# BV100011_Ethernet.net
KiCad netlist of a schematic drawn in Altium Designer
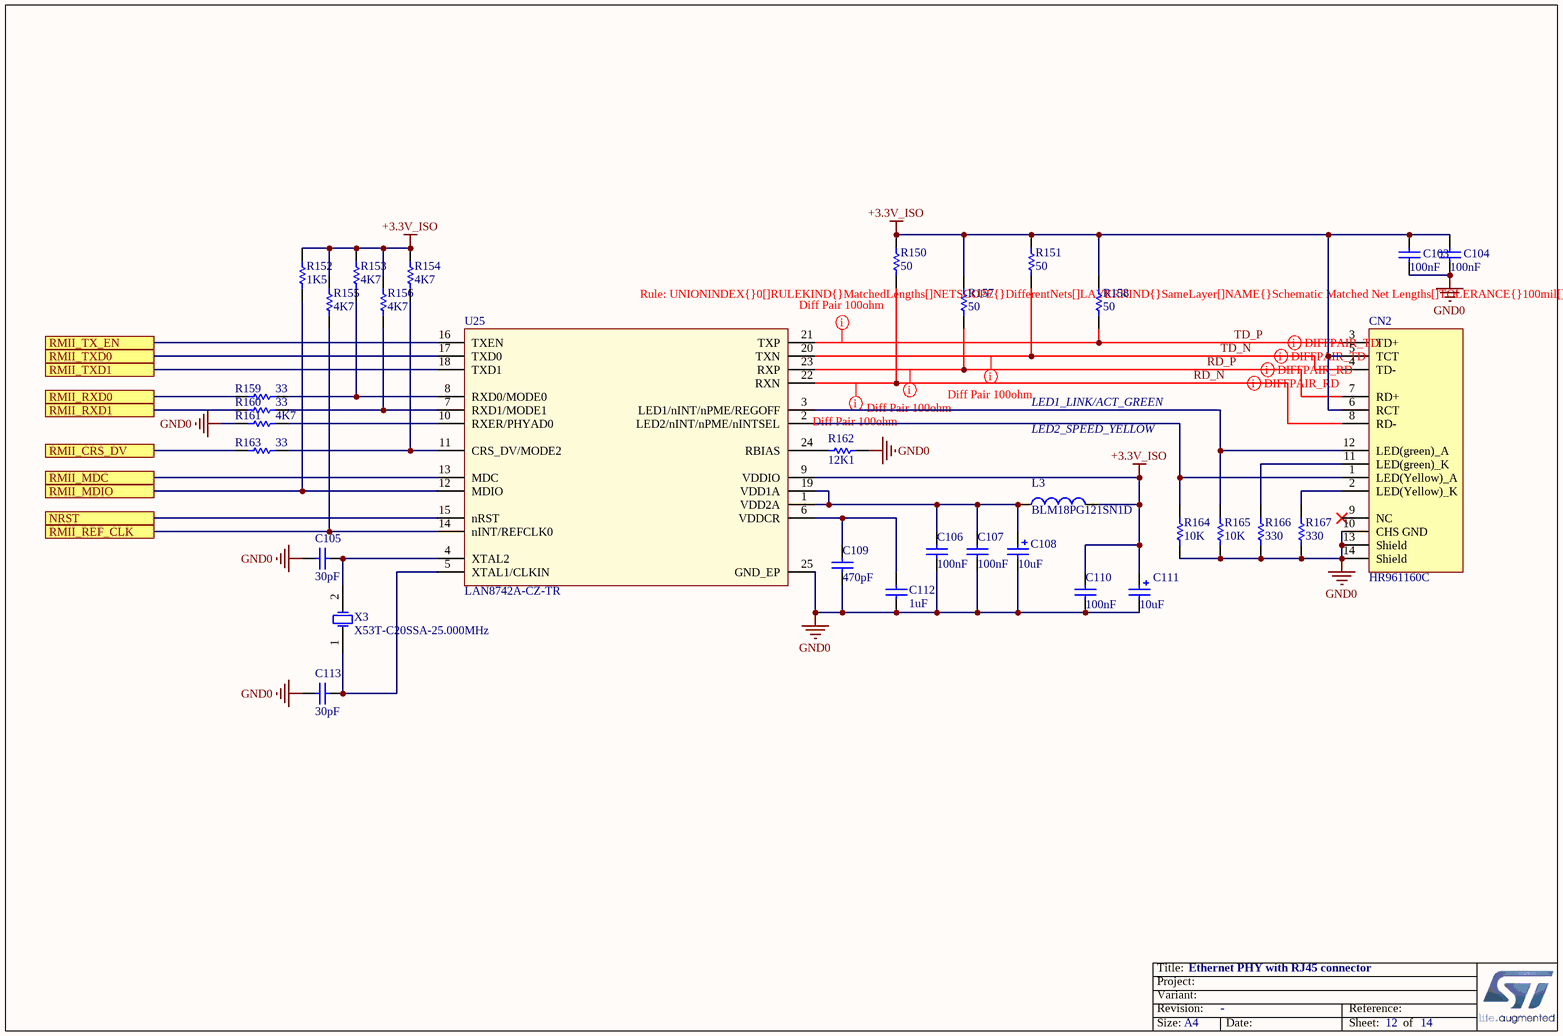
[diagram p0: BV100011_Ethernet.SchDoc]

(export (version "E")
  (design (tool "Eeschema 10.0.6"))
  (components
    (comp (ref "C103")
      (value "100nF")
      (footprint "0402C")
      (description "Capacitor,100nF,16V,X7R,10%,0402,YAGEO")
      (libsource (lib "MCD_TOOLS") (part "Cap_100nF_X7R_10%_0402"))
    )
    (comp (ref "C104")
      (value "100nF")
      (footprint "0402C")
      (description "Capacitor,100nF,16V,X7R,10%,0402,YAGEO")
      (libsource (lib "MCD_TOOLS") (part "Cap_100nF_X7R_10%_0402"))
    )
    (comp (ref "C105")
      (value "30pF")
      (footprint "0603C")
      (description "Capacitor 0402 / 0603 / 0805")
      (libsource (lib "MCD_TOOLS") (part "Capacitor_ST"))
    )
    (comp (ref "C106")
      (value "100nF")
      (footprint "0402C")
      (description "Capacitor,100nF,16V,X7R,10%,0402,YAGEO")
      (libsource (lib "MCD_TOOLS") (part "Cap_100nF_X7R_10%_0402"))
    )
    (comp (ref "C107")
      (value "100nF")
      (footprint "0402C")
      (description "Capacitor,100nF,16V,X7R,10%,0402,YAGEO")
      (libsource (lib "MCD_TOOLS") (part "Cap_100nF_X7R_10%_0402"))
    )
    (comp (ref "C108")
      (value "10uF")
      (footprint "TAN-A")
      (description "Polarized Capacitor,10uF,10V,10%,typeA,VISHAY")
      (libsource (lib "MCD_TOOLS") (part "Cap_10uF_POL_10%_TANA"))
    )
    (comp (ref "C109")
      (value "470pF")
      (footprint "0402C")
      (description "Capacitor,470pF,16V,X7R,10%,0402,YAGEO")
      (libsource (lib "MCD_TOOLS") (part "Cap_470pF_X7R_10%_0402"))
    )
    (comp (ref "C110")
      (value "100nF")
      (footprint "0402C")
      (description "Capacitor,100nF,16V,X7R,10%,0402,YAGEO")
      (libsource (lib "MCD_TOOLS") (part "Cap_100nF_X7R_10%_0402"))
    )
    (comp (ref "C111")
      (value "10uF")
      (footprint "TAN-A")
      (description "Polarized Capacitor,10uF,10V,10%,typeA,VISHAY")
      (libsource (lib "MCD_TOOLS") (part "Cap_10uF_POL_10%_TANA"))
    )
    (comp (ref "C112")
      (value "1uF")
      (footprint "0603C")
      (description "Capacitor,1uF,16V,X5R,10%,0603,YAGEO")
      (libsource (lib "MCD_TOOLS") (part "Cap_1uF_X5R_10%_0603"))
    )
    (comp (ref "C113")
      (value "30pF")
      (footprint "0603C")
      (description "Capacitor 0402 / 0603 / 0805")
      (libsource (lib "MCD_TOOLS") (part "Capacitor_ST"))
    )
    (comp (ref "CN2")
      (value "HR961160C")
      (footprint "RJ45_HR961160C")
      (description "100 Base-TX (Fast Ethernet) SMD RJ45 single port (1x1) with LEDS Integrated Magnetics Connector")
      (libsource (lib "MCD_TOOLS") (part "HR961160C"))
    )
    (comp (ref "L3")
      (value "BLM18PG121SN1D")
      (footprint "0603L")
      (description "Bead,120R,2A,0603,BLM18PG121SN1D,MURATA")
      (libsource (lib "MCD_TOOLS") (part "BEAD_120R_2A_0603"))
    )
    (comp (ref "R150")
      (value "50")
      (footprint "0402R")
      (description "Resistor,50,0402,1%,YAGEO")
      (libsource (lib "MCD_TOOLS") (part "Res_50_1%_0402"))
    )
    (comp (ref "R151")
      (value "50")
      (footprint "0402R")
      (description "Resistor,50,0402,1%,YAGEO")
      (libsource (lib "MCD_TOOLS") (part "Res_50_1%_0402"))
    )
    (comp (ref "R152")
      (value "1K5")
      (footprint "0402R")
      (description "Resistor,1K5,0402,1%,YAGEO")
      (libsource (lib "MCD_TOOLS") (part "Res_1K5_1%_0402"))
    )
    (comp (ref "R153")
      (value "4K7")
      (footprint "0402R")
      (description "Resistor,4K7,0402,1%,YAGEO")
      (libsource (lib "MCD_TOOLS") (part "Res_4K7_1%_0402"))
    )
    (comp (ref "R154")
      (value "4K7")
      (footprint "0402R")
      (description "Resistor,4K7,0402,1%,YAGEO")
      (libsource (lib "MCD_TOOLS") (part "Res_4K7_1%_0402"))
    )
    (comp (ref "R155")
      (value "4K7")
      (footprint "0402R")
      (description "Resistor,4K7,0402,1%,YAGEO")
      (libsource (lib "MCD_TOOLS") (part "Res_4K7_1%_0402"))
    )
    (comp (ref "R156")
      (value "4K7")
      (footprint "0402R")
      (description "Resistor,4K7,0402,1%,YAGEO")
      (libsource (lib "MCD_TOOLS") (part "Res_4K7_1%_0402"))
    )
    (comp (ref "R157")
      (value "50")
      (footprint "0402R")
      (description "Resistor,50,0402,1%,YAGEO")
      (libsource (lib "MCD_TOOLS") (part "Res_50_1%_0402"))
    )
    (comp (ref "R158")
      (value "50")
      (footprint "0402R")
      (description "Resistor,50,0402,1%,YAGEO")
      (libsource (lib "MCD_TOOLS") (part "Res_50_1%_0402"))
    )
    (comp (ref "R159")
      (value "33")
      (footprint "0402R")
      (description "Resistor,33,0402,1%,YAGEO")
      (libsource (lib "MCD_TOOLS") (part "Res_33_1%_0402"))
    )
    (comp (ref "R160")
      (value "33")
      (footprint "0402R")
      (description "Resistor,33,0402,1%,YAGEO")
      (libsource (lib "MCD_TOOLS") (part "Res_33_1%_0402"))
    )
    (comp (ref "R161")
      (value "4K7")
      (footprint "0402R")
      (description "Resistor,4K7,0402,1%,YAGEO")
      (libsource (lib "MCD_TOOLS") (part "Res_4K7_1%_0402"))
    )
    (comp (ref "R162")
      (value "12K1")
      (footprint "0603R")
      (description "Resistor,12K1,0603,1%,VISHAY")
      (libsource (lib "MCD_TOOLS") (part "Res_12K1_1%_0603"))
    )
    (comp (ref "R163")
      (value "33")
      (footprint "0402R")
      (description "Resistor,33,0402,1%,YAGEO")
      (libsource (lib "MCD_TOOLS") (part "Res_33_1%_0402"))
    )
    (comp (ref "R164")
      (value "10K")
      (footprint "0402R")
      (description "Resistor,10K,0402,1%,YAGEO")
      (libsource (lib "MCD_TOOLS") (part "Res_10K_1%_0402"))
    )
    (comp (ref "R165")
      (value "10K")
      (footprint "0402R")
      (description "Resistor,10K,0402,1%,YAGEO")
      (libsource (lib "MCD_TOOLS") (part "Res_10K_1%_0402"))
    )
    (comp (ref "R166")
      (value "330")
      (footprint "0402R")
      (description "Resistor,330,0402,1%,YAGEO")
      (libsource (lib "MCD_TOOLS") (part "Res_330_1%_0402"))
    )
    (comp (ref "R167")
      (value "330")
      (footprint "0402R")
      (description "Resistor,330,0402,1%,YAGEO")
      (libsource (lib "MCD_TOOLS") (part "Res_330_1%_0402"))
    )
    (comp (ref "U25")
      (value "LAN8742A-CZ-TR")
      (footprint "QFN24_0R5_4X4")
      (libsource (lib "MCD_TOOLS") (part "LAN8742A-CZ-TR"))
    )
    (comp (ref "X3")
      (value "X53T-C20SSA-25.000MHz")
      (footprint "XTAL_2SM_5R0X3R2")
      (description "Crystal Oscillator")
      (fields (field (name "PUBLISHER") "Altium Limited"))
      (libsource (lib "MB1137") (part "XTAL_5032"))
    )
  )
  (nets
    (net (code "1") (name "+3.3V_ISO") (class "Default")
      (node (ref "C103") (pin "2") (pinfunction "2_2") (pintype "passive"))
      (node (ref "C104") (pin "2") (pinfunction "2_2") (pintype "passive"))
      (node (ref "C110") (pin "2") (pinfunction "2_2") (pintype "passive"))
      (node (ref "C111") (pin "1") (pinfunction "1_1") (pintype "passive"))
      (node (ref "CN2") (pin "5") (pinfunction "TCT_5") (pintype "passive"))
      (node (ref "CN2") (pin "6") (pinfunction "RCT_6") (pintype "passive"))
      (node (ref "L3") (pin "2") (pinfunction "2_2") (pintype "passive"))
      (node (ref "R150") (pin "1") (pinfunction "1_1") (pintype "passive"))
      (node (ref "R151") (pin "1") (pinfunction "1_1") (pintype "passive"))
      (node (ref "R152") (pin "2") (pinfunction "2_2") (pintype "passive"))
      (node (ref "R153") (pin "2") (pinfunction "2_2") (pintype "passive"))
      (node (ref "R154") (pin "2") (pinfunction "2_2") (pintype "passive"))
      (node (ref "R155") (pin "2") (pinfunction "2_2") (pintype "passive"))
      (node (ref "R156") (pin "2") (pinfunction "2_2") (pintype "passive"))
      (node (ref "R157") (pin "1") (pinfunction "1_1") (pintype "passive"))
      (node (ref "R158") (pin "1") (pinfunction "1_1") (pintype "passive"))
      (node (ref "U25") (pin "9") (pinfunction "VDDIO_9") (pintype "passive"))
    )
    (net (code "2") (name "/NRST") (class "Default")
      (node (ref "U25") (pin "15") (pinfunction "nRST_15") (pintype "passive"))
    )
    (net (code "3") (name "/RD_N") (class "Default")
      (node (ref "CN2") (pin "8") (pinfunction "RD-_8") (pintype "passive"))
      (node (ref "R150") (pin "2") (pinfunction "2_2") (pintype "passive"))
      (node (ref "U25") (pin "22") (pinfunction "RXN_22") (pintype "passive"))
    )
    (net (code "4") (name "/RD_P") (class "Default")
      (node (ref "CN2") (pin "7") (pinfunction "RD+_7") (pintype "passive"))
      (node (ref "R157") (pin "2") (pinfunction "2_2") (pintype "passive"))
      (node (ref "U25") (pin "23") (pinfunction "RXP_23") (pintype "passive"))
    )
    (net (code "5") (name "/RMII_CRS_DV") (class "Default")
      (node (ref "R163") (pin "2") (pinfunction "2_2") (pintype "passive"))
    )
    (net (code "6") (name "/RMII_MDC") (class "Default")
      (node (ref "U25") (pin "13") (pinfunction "MDC_13") (pintype "passive"))
    )
    (net (code "7") (name "/RMII_MDIO") (class "Default")
      (node (ref "R152") (pin "1") (pinfunction "1_1") (pintype "passive"))
      (node (ref "U25") (pin "12") (pinfunction "MDIO_12") (pintype "passive"))
    )
    (net (code "8") (name "/RMII_REF_CLK") (class "Default")
      (node (ref "R155") (pin "1") (pinfunction "1_1") (pintype "passive"))
      (node (ref "U25") (pin "14") (pinfunction "nINT/REFCLK0_14") (pintype "passive"))
    )
    (net (code "9") (name "/RMII_RXD0") (class "Default")
      (node (ref "R159") (pin "2") (pinfunction "2_2") (pintype "passive"))
    )
    (net (code "10") (name "/RMII_RXD1") (class "Default")
      (node (ref "R160") (pin "2") (pinfunction "2_2") (pintype "passive"))
    )
    (net (code "11") (name "/RMII_TXD0") (class "Default")
      (node (ref "U25") (pin "17") (pinfunction "TXD0_17") (pintype "passive"))
    )
    (net (code "12") (name "/RMII_TXD1") (class "Default")
      (node (ref "U25") (pin "18") (pinfunction "TXD1_18") (pintype "passive"))
    )
    (net (code "13") (name "/RMII_TX_EN") (class "Default")
      (node (ref "U25") (pin "16") (pinfunction "TXEN_16") (pintype "passive"))
    )
    (net (code "14") (name "/TD_N") (class "Default")
      (node (ref "CN2") (pin "4") (pinfunction "TD-_4") (pintype "passive"))
      (node (ref "R151") (pin "2") (pinfunction "2_2") (pintype "passive"))
      (node (ref "U25") (pin "20") (pinfunction "TXN_20") (pintype "passive"))
    )
    (net (code "15") (name "/TD_P") (class "Default")
      (node (ref "CN2") (pin "3") (pinfunction "TD+_3") (pintype "passive"))
      (node (ref "R158") (pin "2") (pinfunction "2_2") (pintype "passive"))
      (node (ref "U25") (pin "21") (pinfunction "TXP_21") (pintype "passive"))
    )
    (net (code "16") (name "GND0") (class "Default")
      (node (ref "C103") (pin "1") (pinfunction "1_1") (pintype "passive"))
      (node (ref "C104") (pin "1") (pinfunction "1_1") (pintype "passive"))
      (node (ref "C105") (pin "2") (pinfunction "2_2") (pintype "passive"))
      (node (ref "C106") (pin "1") (pinfunction "1_1") (pintype "passive"))
      (node (ref "C107") (pin "1") (pinfunction "1_1") (pintype "passive"))
      (node (ref "C108") (pin "2") (pinfunction "2_2") (pintype "passive"))
      (node (ref "C109") (pin "1") (pinfunction "1_1") (pintype "passive"))
      (node (ref "C110") (pin "1") (pinfunction "1_1") (pintype "passive"))
      (node (ref "C111") (pin "2") (pinfunction "2_2") (pintype "passive"))
      (node (ref "C112") (pin "1") (pinfunction "1_1") (pintype "passive"))
      (node (ref "C113") (pin "2") (pinfunction "2_2") (pintype "passive"))
      (node (ref "CN2") (pin "10") (pinfunction "CHS_GND_10") (pintype "passive"))
      (node (ref "CN2") (pin "13") (pinfunction "Shield_13") (pintype "passive"))
      (node (ref "CN2") (pin "14") (pinfunction "Shield_14") (pintype "passive"))
      (node (ref "R161") (pin "2") (pinfunction "2_2") (pintype "passive"))
      (node (ref "R162") (pin "2") (pinfunction "2_2") (pintype "passive"))
      (node (ref "R164") (pin "1") (pinfunction "1_1") (pintype "passive"))
      (node (ref "R165") (pin "1") (pinfunction "1_1") (pintype "passive"))
      (node (ref "R166") (pin "1") (pinfunction "1_1") (pintype "passive"))
      (node (ref "R167") (pin "1") (pinfunction "1_1") (pintype "passive"))
      (node (ref "U25") (pin "25") (pinfunction "GND_EP_25") (pintype "passive"))
    )
    (net (code "17") (name "Net-(CN2-LED(Yellow)_A)") (class "Default")
      (node (ref "CN2") (pin "1") (pinfunction "LED(Yellow)_A_1") (pintype "passive"))
      (node (ref "R164") (pin "2") (pinfunction "2_2") (pintype "passive"))
      (node (ref "U25") (pin "2") (pinfunction "LED2/nINT/nPME/nINTSEL_2") (pintype "passive"))
    )
    (net (code "18") (name "Net-(CN2-LED(Yellow)_K)") (class "Default")
      (node (ref "CN2") (pin "2") (pinfunction "LED(Yellow)_K_2") (pintype "passive"))
      (node (ref "R167") (pin "2") (pinfunction "2_2") (pintype "passive"))
    )
    (net (code "19") (name "Net-(CN2-LED(green)_A)") (class "Default")
      (node (ref "CN2") (pin "12") (pinfunction "LED(green)_A_12") (pintype "passive"))
      (node (ref "R165") (pin "2") (pinfunction "2_2") (pintype "passive"))
      (node (ref "U25") (pin "3") (pinfunction "LED1/nINT/nPME/REGOFF_3") (pintype "passive"))
    )
    (net (code "20") (name "Net-(CN2-LED(green)_K)") (class "Default")
      (node (ref "CN2") (pin "11") (pinfunction "LED(green)_K_11") (pintype "passive"))
      (node (ref "R166") (pin "2") (pinfunction "2_2") (pintype "passive"))
    )
    (net (code "21") (name "Net-(U25-CRS_DV{slash}MODE2)") (class "Default")
      (node (ref "R154") (pin "1") (pinfunction "1_1") (pintype "passive"))
      (node (ref "R163") (pin "1") (pinfunction "1_1") (pintype "passive"))
      (node (ref "U25") (pin "11") (pinfunction "CRS_DV/MODE2_11") (pintype "passive"))
    )
    (net (code "22") (name "Net-(U25-RBIAS)") (class "Default")
      (node (ref "R162") (pin "1") (pinfunction "1_1") (pintype "passive"))
      (node (ref "U25") (pin "24") (pinfunction "RBIAS_24") (pintype "passive"))
    )
    (net (code "23") (name "Net-(U25-RXD0{slash}MODE0)") (class "Default")
      (node (ref "R153") (pin "1") (pinfunction "1_1") (pintype "passive"))
      (node (ref "R159") (pin "1") (pinfunction "1_1") (pintype "passive"))
      (node (ref "U25") (pin "8") (pinfunction "RXD0/MODE0_8") (pintype "passive"))
    )
    (net (code "24") (name "Net-(U25-RXD1{slash}MODE1)") (class "Default")
      (node (ref "R156") (pin "1") (pinfunction "1_1") (pintype "passive"))
      (node (ref "R160") (pin "1") (pinfunction "1_1") (pintype "passive"))
      (node (ref "U25") (pin "7") (pinfunction "RXD1/MODE1_7") (pintype "passive"))
    )
    (net (code "25") (name "Net-(U25-RXER{slash}PHYAD0)") (class "Default")
      (node (ref "R161") (pin "1") (pinfunction "1_1") (pintype "passive"))
      (node (ref "U25") (pin "10") (pinfunction "RXER/PHYAD0_10") (pintype "passive"))
    )
    (net (code "26") (name "Net-(U25-VDD1A)") (class "Default")
      (node (ref "C106") (pin "2") (pinfunction "2_2") (pintype "passive"))
      (node (ref "C107") (pin "2") (pinfunction "2_2") (pintype "passive"))
      (node (ref "C108") (pin "1") (pinfunction "1_1") (pintype "passive"))
      (node (ref "L3") (pin "1") (pinfunction "1_1") (pintype "passive"))
      (node (ref "U25") (pin "1") (pinfunction "VDD2A_1") (pintype "passive"))
      (node (ref "U25") (pin "19") (pinfunction "VDD1A_19") (pintype "passive"))
    )
    (net (code "27") (name "Net-(U25-VDDCR)") (class "Default")
      (node (ref "C109") (pin "2") (pinfunction "2_2") (pintype "passive"))
      (node (ref "C112") (pin "2") (pinfunction "2_2") (pintype "passive"))
      (node (ref "U25") (pin "6") (pinfunction "VDDCR_6") (pintype "passive"))
    )
    (net (code "28") (name "Net-(U25-XTAL1{slash}CLKIN)") (class "Default")
      (node (ref "C113") (pin "1") (pinfunction "1_1") (pintype "passive"))
      (node (ref "U25") (pin "5") (pinfunction "XTAL1/CLKIN_5") (pintype "passive"))
      (node (ref "X3") (pin "1") (pinfunction "OSC1_1") (pintype "passive"))
    )
    (net (code "29") (name "Net-(U25-XTAL2)") (class "Default")
      (node (ref "C105") (pin "1") (pinfunction "1_1") (pintype "passive"))
      (node (ref "U25") (pin "4") (pinfunction "XTAL2_4") (pintype "passive"))
      (node (ref "X3") (pin "2") (pinfunction "OSC2_2") (pintype "passive"))
    )
    (net (code "30") (name "unconnected-(CN2-NC-Pad9)") (class "Default")
      (node (ref "CN2") (pin "9") (pinfunction "NC_9") (pintype "passive+no_connect"))
    )
  )
)
